# cryptocape.net
KiCad netlist of a schematic drawn in EAGLE
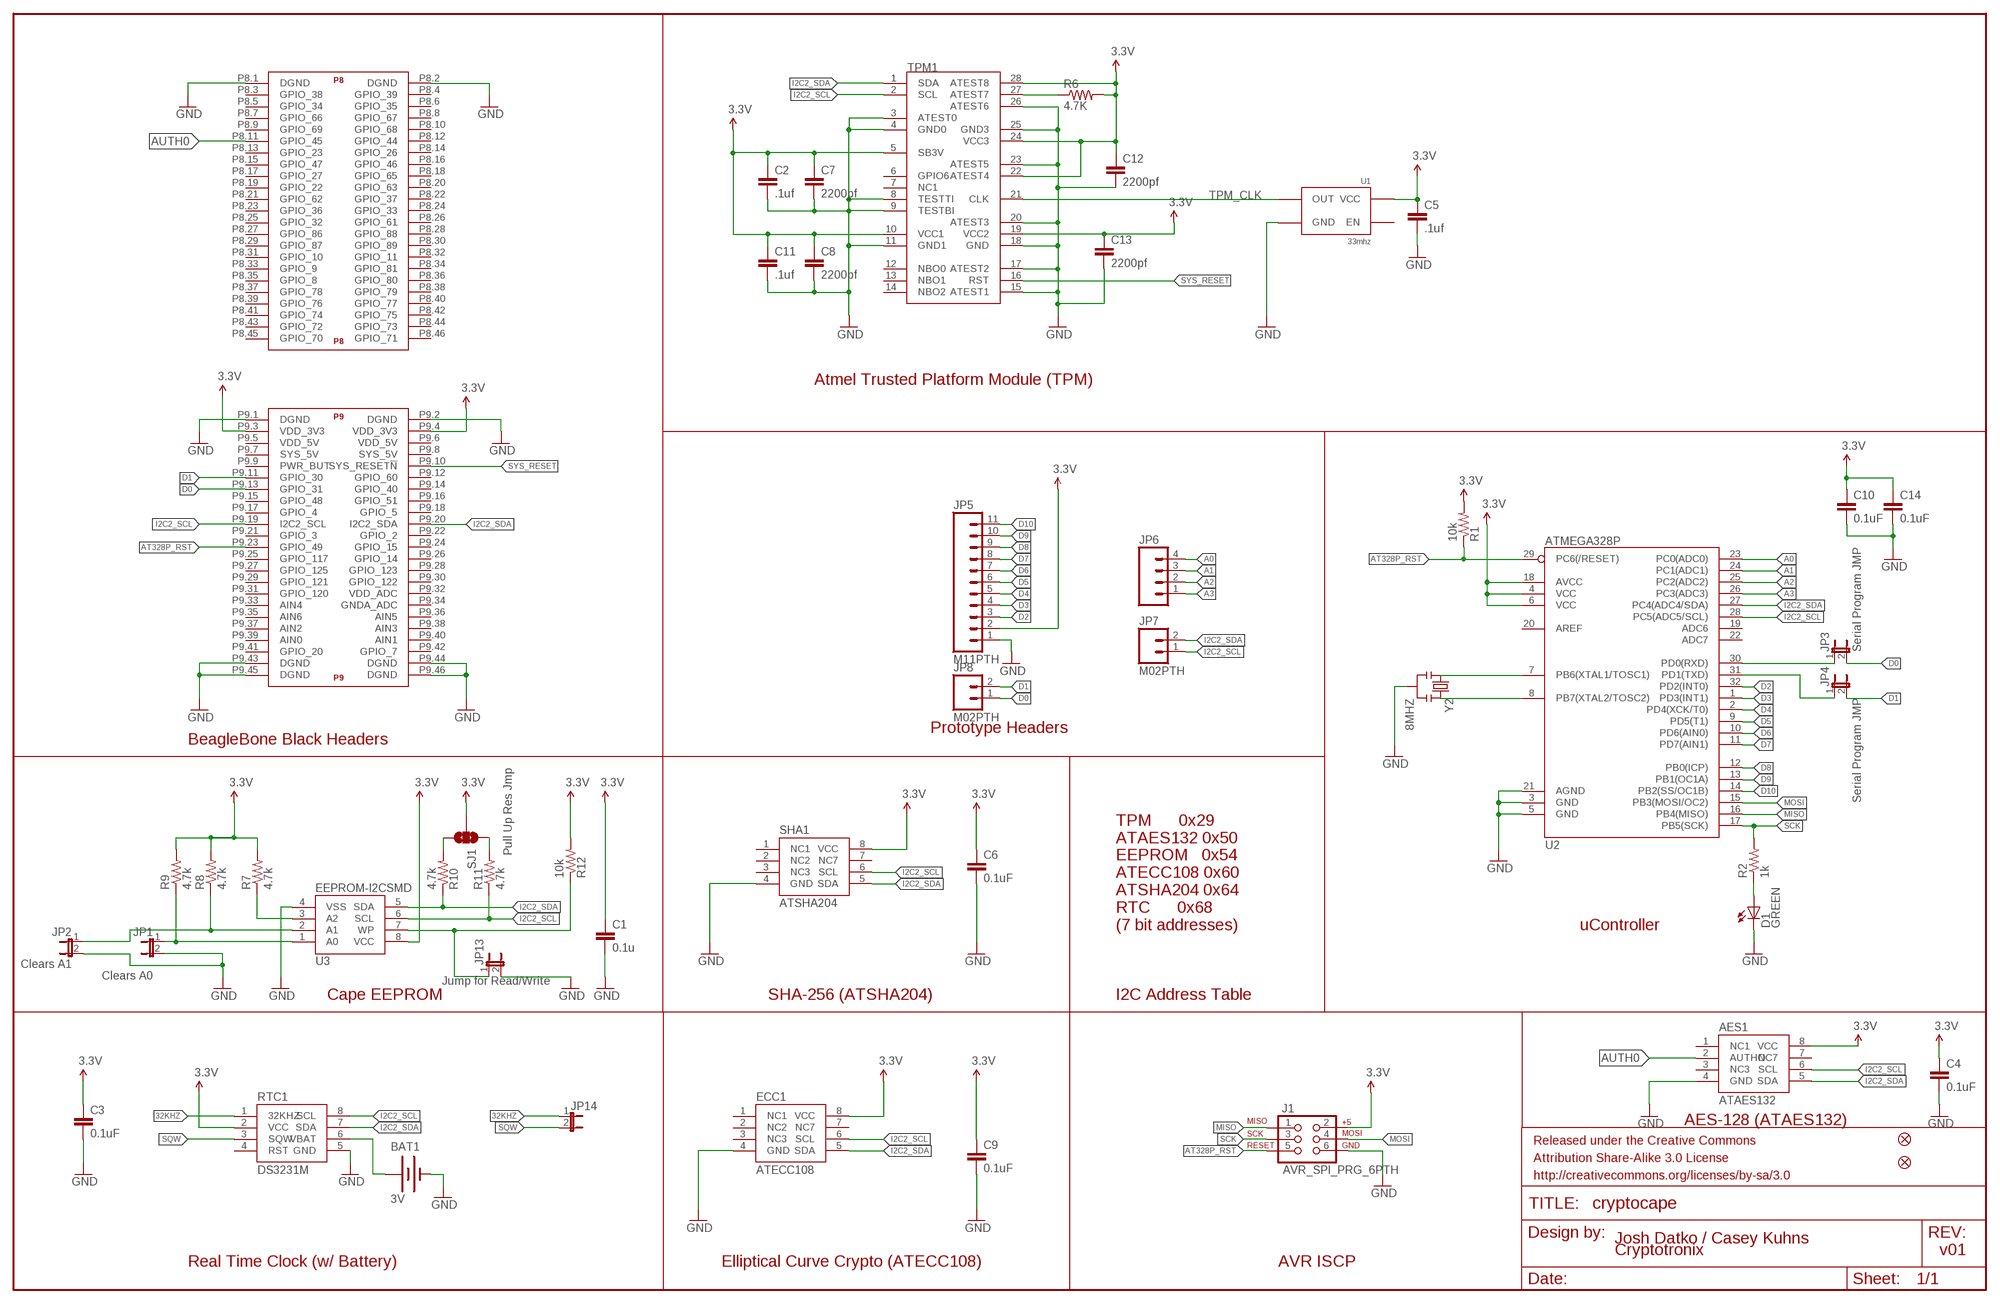
[diagram p0: schematic, sheet 1]

(export (version "E")
  (design (tool "Eeschema 10.0.6"))
  (components
    (comp (ref "AES1")
      (value "ATAES132")
      (footprint "eagle-import:SOIC8")
      (libsource (lib "eagle-import") (part "ATAES132"))
    )
    (comp (ref "BAT1")
      (value "3V")
      (footprint "eagle-import:BATTCON_12MM")
      (libsource (lib "eagle-import") (part "BATTERY12MM"))
    )
    (comp (ref "C1")
      (value "0.1u")
      (footprint "eagle-import:0603-CAP")
      (libsource (lib "eagle-import") (part "0.1UF-25V(+80/-20%)(0603)"))
    )
    (comp (ref "C2")
      (value ".1uf")
      (footprint "eagle-import:0603-CAP")
      (libsource (lib "eagle-import") (part "0.1UF-25V(+80/-20%)(0603)"))
    )
    (comp (ref "C3")
      (value "0.1uF")
      (footprint "eagle-import:0603-CAP")
      (libsource (lib "eagle-import") (part "0.1UF-25V(+80/-20%)(0603)"))
    )
    (comp (ref "C4")
      (value "0.1uF")
      (footprint "eagle-import:0603-CAP")
      (libsource (lib "eagle-import") (part "0.1UF-25V(+80/-20%)(0603)"))
    )
    (comp (ref "C5")
      (value ".1uf")
      (footprint "eagle-import:0603-CAP")
      (libsource (lib "eagle-import") (part "0.1UF-25V(+80/-20%)(0603)"))
    )
    (comp (ref "C6")
      (value "0.1uF")
      (footprint "eagle-import:0603-CAP")
      (libsource (lib "eagle-import") (part "0.1UF-25V(+80/-20%)(0603)"))
    )
    (comp (ref "C7")
      (value "2200pf")
      (footprint "eagle-import:0603-CAP")
      (libsource (lib "eagle-import") (part "2.2NF/2200PF-50V-10%(0603)"))
    )
    (comp (ref "C8")
      (value "2200pf")
      (footprint "eagle-import:0603-CAP")
      (libsource (lib "eagle-import") (part "2.2NF/2200PF-50V-10%(0603)"))
    )
    (comp (ref "C9")
      (value "0.1uF")
      (footprint "eagle-import:0603-CAP")
      (libsource (lib "eagle-import") (part "0.1UF-25V(+80/-20%)(0603)"))
    )
    (comp (ref "C10")
      (value "0.1uF")
      (footprint "eagle-import:0603-CAP")
      (libsource (lib "eagle-import") (part "0.1UF-25V(+80/-20%)(0603)"))
    )
    (comp (ref "C11")
      (value ".1uf")
      (footprint "eagle-import:0603-CAP")
      (libsource (lib "eagle-import") (part "0.1UF-25V(+80/-20%)(0603)"))
    )
    (comp (ref "C12")
      (value "2200pf")
      (footprint "eagle-import:0603-CAP")
      (libsource (lib "eagle-import") (part "2.2NF/2200PF-50V-10%(0603)"))
    )
    (comp (ref "C13")
      (value "2200pf")
      (footprint "eagle-import:0603-CAP")
      (libsource (lib "eagle-import") (part "2.2NF/2200PF-50V-10%(0603)"))
    )
    (comp (ref "C14")
      (value "0.1uF")
      (footprint "eagle-import:0603-CAP")
      (libsource (lib "eagle-import") (part "0.1UF-25V(+80/-20%)(0603)"))
    )
    (comp (ref "D1")
      (value "GREEN")
      (footprint "eagle-import:LED-0603")
      (libsource (lib "eagle-import") (part "LED-GREEN0603"))
    )
    (comp (ref "ECC1")
      (value "ATECC108")
      (footprint "eagle-import:SOIC8")
      (libsource (lib "eagle-import") (part "ATECC108"))
    )
    (comp (ref "FID1")
      (value "FIDUCIAL1X2")
      (footprint "eagle-import:FIDUCIAL-1X2")
      (libsource (lib "eagle-import") (part "FIDUCIAL1X2"))
    )
    (comp (ref "FID2")
      (value "FIDUCIAL1X2")
      (footprint "eagle-import:FIDUCIAL-1X2")
      (libsource (lib "eagle-import") (part "FIDUCIAL1X2"))
    )
    (comp (ref "FRAME1")
      (value "FRAME-LEDGER")
      (footprint "eagle-import:CREATIVE_COMMONS")
      (libsource (lib "eagle-import") (part "FRAME-LEDGER"))
    )
    (comp (ref "J1")
      (value "AVR_SPI_PRG_6PTH")
      (footprint "eagle-import:2X3")
      (libsource (lib "eagle-import") (part "AVR_SPI_PRG_6PTH"))
    )
    (comp (ref "JP1")
      (value "Clears A0")
      (footprint "eagle-import:SJ_2S-NO")
      (libsource (lib "eagle-import") (part "JUMPER-2SMD-NO"))
    )
    (comp (ref "JP2")
      (value "Clears A1")
      (footprint "eagle-import:SJ_2S-NO")
      (libsource (lib "eagle-import") (part "JUMPER-2SMD-NO"))
    )
    (comp (ref "JP3")
      (value "Serial Program JMP")
      (footprint "eagle-import:1X02")
      (libsource (lib "eagle-import") (part "JUMPER-2PTH"))
    )
    (comp (ref "JP4")
      (value "Serial Program JMP")
      (footprint "eagle-import:1X02")
      (libsource (lib "eagle-import") (part "JUMPER-2PTH"))
    )
    (comp (ref "JP5")
      (value "M11PTH")
      (footprint "eagle-import:1X11")
      (libsource (lib "eagle-import") (part "M11PTH"))
    )
    (comp (ref "JP6")
      (value "M04PTH")
      (footprint "eagle-import:1X04")
      (libsource (lib "eagle-import") (part "M04PTH"))
    )
    (comp (ref "JP7")
      (value "M02PTH")
      (footprint "eagle-import:1X02")
      (libsource (lib "eagle-import") (part "M02PTH"))
    )
    (comp (ref "JP8")
      (value "M02PTH")
      (footprint "eagle-import:1X02")
      (libsource (lib "eagle-import") (part "M02PTH"))
    )
    (comp (ref "JP13")
      (value "Jump for Read/Write")
      (footprint "eagle-import:1X02")
      (libsource (lib "eagle-import") (part "JUMPER-2PTH"))
    )
    (comp (ref "JP14")
      (value "JUMPER-2PTH")
      (footprint "eagle-import:1X02")
      (libsource (lib "eagle-import") (part "JUMPER-2PTH"))
    )
    (comp (ref "R1")
      (value "10k")
      (footprint "eagle-import:0603-RES")
      (libsource (lib "eagle-import") (part "10KOHM1/10W1%(0603)0603"))
    )
    (comp (ref "R2")
      (value "1k")
      (footprint "eagle-import:0603-RES")
      (libsource (lib "eagle-import") (part "1K-1%"))
    )
    (comp (ref "R6")
      (value "4.7K")
      (footprint "eagle-import:0603")
      (libsource (lib "eagle-import") (part "4.7KOHM1/10W1%(0603)"))
    )
    (comp (ref "R7")
      (value "4.7k")
      (footprint "eagle-import:0603")
      (libsource (lib "eagle-import") (part "4.7KOHM1/10W1%(0603)"))
    )
    (comp (ref "R8")
      (value "4.7k")
      (footprint "eagle-import:0603")
      (libsource (lib "eagle-import") (part "4.7KOHM1/10W1%(0603)"))
    )
    (comp (ref "R9")
      (value "4.7k")
      (footprint "eagle-import:0603")
      (libsource (lib "eagle-import") (part "4.7KOHM1/10W1%(0603)"))
    )
    (comp (ref "R10")
      (value "4.7k")
      (footprint "eagle-import:0603")
      (fields (field (name "PROD_ID") "RES-07857"))
      (libsource (lib "eagle-import") (part "4.7KOHM1/10W1%(0603)"))
    )
    (comp (ref "R11")
      (value "4.7k")
      (footprint "eagle-import:0603")
      (fields (field (name "PROD_ID") "RES-07857"))
      (libsource (lib "eagle-import") (part "4.7KOHM1/10W1%(0603)"))
    )
    (comp (ref "R12")
      (value "10k")
      (footprint "eagle-import:0603-RES")
      (libsource (lib "eagle-import") (part "10KOHM1/10W1%(0603)0603"))
    )
    (comp (ref "RTC1")
      (value "DS3231M")
      (footprint "eagle-import:SOIC8")
      (libsource (lib "eagle-import") (part "DS3231M"))
    )
    (comp (ref "SHA1")
      (value "ATSHA204")
      (footprint "eagle-import:SOIC8")
      (libsource (lib "eagle-import") (part "ATSHA204"))
    )
    (comp (ref "SJ1")
      (value "Pull Up Res Jmp")
      (footprint "eagle-import:SJ_3_PASTE1&2&3")
      (libsource (lib "eagle-import") (part "SOLDERJUMPER_2WAYPASTE1&2&3"))
    )
    (comp (ref "TPM1")
      (value "AT97SC3204T")
      (footprint "eagle-import:TSSOP28")
      (libsource (lib "eagle-import") (part "AT97SC3204T"))
    )
    (comp (ref "U$2")
      (value "BEAGLE_BONE_BLACK_CAPE")
      (footprint "eagle-import:BEAGLE_BONE_BLACK_CAPE")
      (libsource (lib "eagle-import") (part "BEAGLE_BONE_BLACK_CAPE"))
    )
    (comp (ref "U1")
      (value "33mhz")
      (footprint "eagle-import:CRYSTAL-OSC-SMD-5X3.2")
      (libsource (lib "eagle-import") (part "OSCILLATOR"))
    )
    (comp (ref "U2")
      (value "ATMEGA328P")
      (footprint "eagle-import:TQFP32-08")
      (libsource (lib "eagle-import") (part "ATMEGA328_SMT"))
    )
    (comp (ref "U3")
      (value "EEPROM-I2CSMD")
      (footprint "eagle-import:SO08")
      (libsource (lib "eagle-import") (part "EEPROM-I2CSMD"))
    )
    (comp (ref "Y2")
      (value "8MHZ")
      (footprint "eagle-import:RESONATOR-SMD")
      (libsource (lib "eagle-import") (part "RESONATOR8MHZ"))
    )
  )
  (nets
    (net (code "1") (name "/TPM_CLK") (class "Default")
      (node (ref "TPM1") (pin "21") (pinfunction "CLK_21") (pintype "bidirectional"))
      (node (ref "U1") (pin "3") (pinfunction "OUT_3") (pintype "bidirectional"))
    )
    (net (code "2") (name "3.3V") (class "Default")
      (node (ref "AES1") (pin "8") (pinfunction "VCC_8") (pintype "power_in"))
      (node (ref "C1") (pin "1") (pinfunction "1_1") (pintype "passive"))
      (node (ref "C10") (pin "1") (pinfunction "1_1") (pintype "passive"))
      (node (ref "C11") (pin "1") (pinfunction "1_1") (pintype "passive"))
      (node (ref "C12") (pin "1") (pinfunction "1_1") (pintype "passive"))
      (node (ref "C13") (pin "1") (pinfunction "1_1") (pintype "passive"))
      (node (ref "C14") (pin "1") (pinfunction "1_1") (pintype "passive"))
      (node (ref "C2") (pin "1") (pinfunction "1_1") (pintype "passive"))
      (node (ref "C3") (pin "1") (pinfunction "1_1") (pintype "passive"))
      (node (ref "C4") (pin "1") (pinfunction "1_1") (pintype "passive"))
      (node (ref "C5") (pin "1") (pinfunction "1_1") (pintype "passive"))
      (node (ref "C6") (pin "1") (pinfunction "1_1") (pintype "passive"))
      (node (ref "C7") (pin "1") (pinfunction "1_1") (pintype "passive"))
      (node (ref "C8") (pin "1") (pinfunction "1_1") (pintype "passive"))
      (node (ref "C9") (pin "1") (pinfunction "1_1") (pintype "passive"))
      (node (ref "ECC1") (pin "8") (pinfunction "VCC_8") (pintype "power_in"))
      (node (ref "J1") (pin "2") (pinfunction "2_2") (pintype "passive"))
      (node (ref "JP5") (pin "2") (pinfunction "2_2") (pintype "passive"))
      (node (ref "R1") (pin "2") (pinfunction "2_2") (pintype "passive"))
      (node (ref "R12") (pin "2") (pinfunction "2_2") (pintype "passive"))
      (node (ref "R6") (pin "2") (pinfunction "2_2") (pintype "passive"))
      (node (ref "R7") (pin "2") (pinfunction "2_2") (pintype "passive"))
      (node (ref "R8") (pin "2") (pinfunction "2_2") (pintype "passive"))
      (node (ref "R9") (pin "2") (pinfunction "2_2") (pintype "passive"))
      (node (ref "RTC1") (pin "2") (pinfunction "VCC_2") (pintype "power_in"))
      (node (ref "SHA1") (pin "8") (pinfunction "VCC_8") (pintype "power_in"))
      (node (ref "SJ1") (pin "2") (pinfunction "2_2") (pintype "passive"))
      (node (ref "TPM1") (pin "10") (pinfunction "VCC1_10") (pintype "power_in"))
      (node (ref "TPM1") (pin "19") (pinfunction "VCC2_19") (pintype "power_in"))
      (node (ref "TPM1") (pin "22") (pinfunction "ATEST4_22") (pintype "power_in"))
      (node (ref "TPM1") (pin "24") (pinfunction "VCC3_24") (pintype "power_in"))
      (node (ref "TPM1") (pin "28") (pinfunction "ATEST8_28") (pintype "power_in"))
      (node (ref "TPM1") (pin "5") (pinfunction "SB3V_5") (pintype "power_in"))
      (node (ref "U$2") (pin "P9.3") (pinfunction "VDD_3V3_P9.3") (pintype "bidirectional"))
      (node (ref "U$2") (pin "P9.4") (pinfunction "VDD_3V3_P9.4") (pintype "bidirectional"))
      (node (ref "U1") (pin "4") (pinfunction "VCC_4") (pintype "bidirectional"))
      (node (ref "U2") (pin "18") (pinfunction "AVCC_18") (pintype "bidirectional"))
      (node (ref "U2") (pin "4") (pinfunction "VCC_4") (pintype "bidirectional"))
      (node (ref "U2") (pin "6") (pinfunction "VCC_6") (pintype "bidirectional"))
      (node (ref "U3") (pin "8") (pinfunction "VCC_8") (pintype "power_in"))
    )
    (net (code "3") (name "32KHZ") (class "Default")
      (node (ref "JP14") (pin "1") (pinfunction "1_1") (pintype "passive"))
      (node (ref "RTC1") (pin "1") (pinfunction "32KHZ_1") (pintype "output"))
    )
    (net (code "4") (name "A0") (class "Default")
      (node (ref "JP6") (pin "4") (pinfunction "4_4") (pintype "passive"))
      (node (ref "U2") (pin "23") (pinfunction "PC0(ADC0)_23") (pintype "bidirectional"))
    )
    (net (code "5") (name "A1") (class "Default")
      (node (ref "JP6") (pin "3") (pinfunction "3_3") (pintype "passive"))
      (node (ref "U2") (pin "24") (pinfunction "PC1(ADC1)_24") (pintype "bidirectional"))
    )
    (net (code "6") (name "A2") (class "Default")
      (node (ref "JP6") (pin "2") (pinfunction "2_2") (pintype "passive"))
      (node (ref "U2") (pin "25") (pinfunction "PC2(ADC2)_25") (pintype "bidirectional"))
    )
    (net (code "7") (name "A3") (class "Default")
      (node (ref "JP6") (pin "1") (pinfunction "1_1") (pintype "passive"))
      (node (ref "U2") (pin "26") (pinfunction "PC3(ADC3)_26") (pintype "bidirectional"))
    )
    (net (code "8") (name "AT328P_RST") (class "Default")
      (node (ref "J1") (pin "5") (pinfunction "5_5") (pintype "passive"))
      (node (ref "R1") (pin "1") (pinfunction "1_1") (pintype "passive"))
      (node (ref "U$2") (pin "P9.23") (pinfunction "GPIO_49_P9.23") (pintype "bidirectional"))
      (node (ref "U2") (pin "29") (pinfunction "PC6(/RESET)_29") (pintype "bidirectional"))
    )
    (net (code "9") (name "AUTH0") (class "Default")
      (node (ref "AES1") (pin "2") (pinfunction "AUTHO_2") (pintype "bidirectional"))
      (node (ref "U$2") (pin "P8.11") (pinfunction "GPIO_45_P8.11") (pintype "bidirectional"))
    )
    (net (code "10") (name "D0") (class "Default")
      (node (ref "JP3") (pin "2") (pinfunction "2_2") (pintype "passive"))
      (node (ref "JP8") (pin "1") (pinfunction "1_1") (pintype "passive"))
      (node (ref "U$2") (pin "P9.13") (pinfunction "GPIO_31_P9.13") (pintype "bidirectional"))
    )
    (net (code "11") (name "D1") (class "Default")
      (node (ref "JP4") (pin "2") (pinfunction "2_2") (pintype "passive"))
      (node (ref "JP8") (pin "2") (pinfunction "2_2") (pintype "passive"))
      (node (ref "U$2") (pin "P9.11") (pinfunction "GPIO_30_P9.11") (pintype "bidirectional"))
    )
    (net (code "12") (name "D2") (class "Default")
      (node (ref "JP5") (pin "3") (pinfunction "3_3") (pintype "passive"))
      (node (ref "U2") (pin "32") (pinfunction "PD2(INT0)_32") (pintype "bidirectional"))
    )
    (net (code "13") (name "D3") (class "Default")
      (node (ref "JP5") (pin "4") (pinfunction "4_4") (pintype "passive"))
      (node (ref "U2") (pin "1") (pinfunction "PD3(INT1)_1") (pintype "bidirectional"))
    )
    (net (code "14") (name "D4") (class "Default")
      (node (ref "JP5") (pin "5") (pinfunction "5_5") (pintype "passive"))
      (node (ref "U2") (pin "2") (pinfunction "PD4(XCK/T0)_2") (pintype "bidirectional"))
    )
    (net (code "15") (name "D5") (class "Default")
      (node (ref "JP5") (pin "6") (pinfunction "6_6") (pintype "passive"))
      (node (ref "U2") (pin "9") (pinfunction "PD5(T1)_9") (pintype "bidirectional"))
    )
    (net (code "16") (name "D6") (class "Default")
      (node (ref "JP5") (pin "7") (pinfunction "7_7") (pintype "passive"))
      (node (ref "U2") (pin "10") (pinfunction "PD6(AIN0)_10") (pintype "bidirectional"))
    )
    (net (code "17") (name "D7") (class "Default")
      (node (ref "JP5") (pin "8") (pinfunction "8_8") (pintype "passive"))
      (node (ref "U2") (pin "11") (pinfunction "PD7(AIN1)_11") (pintype "bidirectional"))
    )
    (net (code "18") (name "D8") (class "Default")
      (node (ref "JP5") (pin "9") (pinfunction "9_9") (pintype "passive"))
      (node (ref "U2") (pin "12") (pinfunction "PB0(ICP)_12") (pintype "bidirectional"))
    )
    (net (code "19") (name "D9") (class "Default")
      (node (ref "JP5") (pin "10") (pinfunction "10_10") (pintype "passive"))
      (node (ref "U2") (pin "13") (pinfunction "PB1(OC1A)_13") (pintype "bidirectional"))
    )
    (net (code "20") (name "D10") (class "Default")
      (node (ref "JP5") (pin "11") (pinfunction "11_11") (pintype "passive"))
      (node (ref "U2") (pin "14") (pinfunction "PB2(SS/OC1B)_14") (pintype "bidirectional"))
    )
    (net (code "21") (name "GND") (class "Default")
      (node (ref "AES1") (pin "4") (pinfunction "GND_4") (pintype "power_in"))
      (node (ref "BAT1") (pin "GND") (pinfunction "-_GND") (pintype "power_in"))
      (node (ref "C1") (pin "2") (pinfunction "2_2") (pintype "passive"))
      (node (ref "C10") (pin "2") (pinfunction "2_2") (pintype "passive"))
      (node (ref "C11") (pin "2") (pinfunction "2_2") (pintype "passive"))
      (node (ref "C12") (pin "2") (pinfunction "2_2") (pintype "passive"))
      (node (ref "C13") (pin "2") (pinfunction "2_2") (pintype "passive"))
      (node (ref "C14") (pin "2") (pinfunction "2_2") (pintype "passive"))
      (node (ref "C2") (pin "2") (pinfunction "2_2") (pintype "passive"))
      (node (ref "C3") (pin "2") (pinfunction "2_2") (pintype "passive"))
      (node (ref "C4") (pin "2") (pinfunction "2_2") (pintype "passive"))
      (node (ref "C5") (pin "2") (pinfunction "2_2") (pintype "passive"))
      (node (ref "C6") (pin "2") (pinfunction "2_2") (pintype "passive"))
      (node (ref "C7") (pin "2") (pinfunction "2_2") (pintype "passive"))
      (node (ref "C8") (pin "2") (pinfunction "2_2") (pintype "passive"))
      (node (ref "C9") (pin "2") (pinfunction "2_2") (pintype "passive"))
      (node (ref "D1") (pin "C") (pinfunction "C_C") (pintype "passive"))
      (node (ref "ECC1") (pin "4") (pinfunction "GND_4") (pintype "power_in"))
      (node (ref "J1") (pin "6") (pinfunction "6_6") (pintype "passive"))
      (node (ref "JP1") (pin "2") (pinfunction "2_2") (pintype "passive"))
      (node (ref "JP13") (pin "2") (pinfunction "2_2") (pintype "passive"))
      (node (ref "JP2") (pin "2") (pinfunction "2_2") (pintype "passive"))
      (node (ref "JP5") (pin "1") (pinfunction "1_1") (pintype "passive"))
      (node (ref "RTC1") (pin "5") (pinfunction "GND_5") (pintype "power_in"))
      (node (ref "SHA1") (pin "4") (pinfunction "GND_4") (pintype "power_in"))
      (node (ref "TPM1") (pin "11") (pinfunction "GND1_11") (pintype "power_in"))
      (node (ref "TPM1") (pin "15") (pinfunction "ATEST1_15") (pintype "power_in"))
      (node (ref "TPM1") (pin "17") (pinfunction "ATEST2_17") (pintype "power_in"))
      (node (ref "TPM1") (pin "18") (pinfunction "GND_18") (pintype "power_in"))
      (node (ref "TPM1") (pin "20") (pinfunction "ATEST3_20") (pintype "power_in"))
      (node (ref "TPM1") (pin "23") (pinfunction "ATEST5_23") (pintype "power_in"))
      (node (ref "TPM1") (pin "25") (pinfunction "GND3_25") (pintype "power_in"))
      (node (ref "TPM1") (pin "26") (pinfunction "ATEST6_26") (pintype "power_in"))
      (node (ref "TPM1") (pin "3") (pinfunction "ATEST0_3") (pintype "power_in"))
      (node (ref "TPM1") (pin "4") (pinfunction "GND0_4") (pintype "power_in"))
      (node (ref "TPM1") (pin "8") (pinfunction "TESTTI_8") (pintype "power_in"))
      (node (ref "TPM1") (pin "9") (pinfunction "TESTBI_9") (pintype "power_in"))
      (node (ref "U$2") (pin "P8.1") (pinfunction "DGND_P8.1") (pintype "bidirectional"))
      (node (ref "U$2") (pin "P8.2") (pinfunction "DGND_P8.2") (pintype "bidirectional"))
      (node (ref "U$2") (pin "P9.1") (pinfunction "DGND_P9.1") (pintype "bidirectional"))
      (node (ref "U$2") (pin "P9.2") (pinfunction "DGND_P9.2") (pintype "bidirectional"))
      (node (ref "U$2") (pin "P9.43") (pinfunction "DGND_P9.43") (pintype "bidirectional"))
      (node (ref "U$2") (pin "P9.44") (pinfunction "DGND_P9.44") (pintype "bidirectional"))
      (node (ref "U$2") (pin "P9.45") (pinfunction "DGND_P9.45") (pintype "bidirectional"))
      (node (ref "U$2") (pin "P9.46") (pinfunction "DGND_P9.46") (pintype "bidirectional"))
      (node (ref "U1") (pin "2") (pinfunction "GND_2") (pintype "bidirectional"))
      (node (ref "U2") (pin "21") (pinfunction "AGND_21") (pintype "bidirectional"))
      (node (ref "U2") (pin "3") (pinfunction "GND_3") (pintype "bidirectional"))
      (node (ref "U2") (pin "5") (pinfunction "GND_5") (pintype "bidirectional"))
      (node (ref "U3") (pin "4") (pinfunction "VSS_4") (pintype "power_in"))
      (node (ref "Y2") (pin "2") (pinfunction "2_2") (pintype "passive"))
    )
    (net (code "22") (name "I2C2_SCL") (class "Default")
      (node (ref "AES1") (pin "6") (pinfunction "SCL_6") (pintype "bidirectional"))
      (node (ref "ECC1") (pin "6") (pinfunction "SCL_6") (pintype "bidirectional"))
      (node (ref "JP7") (pin "1") (pinfunction "1_1") (pintype "passive"))
      (node (ref "R11") (pin "1") (pinfunction "1_1") (pintype "passive"))
      (node (ref "RTC1") (pin "8") (pinfunction "SCL_8") (pintype "bidirectional"))
      (node (ref "SHA1") (pin "6") (pinfunction "SCL_6") (pintype "bidirectional"))
      (node (ref "TPM1") (pin "2") (pinfunction "SCL_2") (pintype "bidirectional"))
      (node (ref "U$2") (pin "P9.19") (pinfunction "I2C2_SCL_P9.19") (pintype "bidirectional"))
      (node (ref "U2") (pin "28") (pinfunction "PC5(ADC5/SCL)_28") (pintype "bidirectional"))
      (node (ref "U3") (pin "6") (pinfunction "SCL_6") (pintype "bidirectional"))
    )
    (net (code "23") (name "I2C2_SDA") (class "Default")
      (node (ref "AES1") (pin "5") (pinfunction "SDA_5") (pintype "bidirectional"))
      (node (ref "ECC1") (pin "5") (pinfunction "SDA_5") (pintype "bidirectional"))
      (node (ref "JP7") (pin "2") (pinfunction "2_2") (pintype "passive"))
      (node (ref "R10") (pin "1") (pinfunction "1_1") (pintype "passive"))
      (node (ref "RTC1") (pin "7") (pinfunction "SDA_7") (pintype "bidirectional"))
      (node (ref "SHA1") (pin "5") (pinfunction "SDA_5") (pintype "bidirectional"))
      (node (ref "TPM1") (pin "1") (pinfunction "SDA_1") (pintype "bidirectional"))
      (node (ref "U$2") (pin "P9.20") (pinfunction "I2C2_SDA_P9.20") (pintype "bidirectional"))
      (node (ref "U2") (pin "27") (pinfunction "PC4(ADC4/SDA)_27") (pintype "bidirectional"))
      (node (ref "U3") (pin "5") (pinfunction "SDA_5") (pintype "bidirectional"))
    )
    (net (code "24") (name "MISO") (class "Default")
      (node (ref "J1") (pin "1") (pinfunction "1_1") (pintype "passive"))
      (node (ref "U2") (pin "16") (pinfunction "PB4(MISO)_16") (pintype "bidirectional"))
    )
    (net (code "25") (name "MOSI") (class "Default")
      (node (ref "J1") (pin "4") (pinfunction "4_4") (pintype "passive"))
      (node (ref "U2") (pin "15") (pinfunction "PB3(MOSI/OC2)_15") (pintype "bidirectional"))
    )
    (net (code "26") (name "Net-(BAT1-+)") (class "Default")
      (node (ref "BAT1") (pin "PWR@1") (pinfunction "+_PWR@1") (pintype "power_in"))
      (node (ref "RTC1") (pin "6") (pinfunction "VBAT_6") (pintype "power_in"))
    )
    (net (code "27") (name "Net-(D1-PadA)") (class "Default")
      (node (ref "D1") (pin "A") (pinfunction "A_A") (pintype "passive"))
      (node (ref "R2") (pin "1") (pinfunction "1_1") (pintype "passive"))
    )
    (net (code "28") (name "Net-(R10-Pad2)") (class "Default")
      (node (ref "R10") (pin "2") (pinfunction "2_2") (pintype "passive"))
      (node (ref "SJ1") (pin "3") (pinfunction "3_3") (pintype "passive"))
    )
    (net (code "29") (name "Net-(R11-Pad2)") (class "Default")
      (node (ref "R11") (pin "2") (pinfunction "2_2") (pintype "passive"))
      (node (ref "SJ1") (pin "1") (pinfunction "1_1") (pintype "passive"))
    )
    (net (code "30") (name "Net-(TPM1-ATEST7)") (class "Default")
      (node (ref "R6") (pin "1") (pinfunction "1_1") (pintype "passive"))
      (node (ref "TPM1") (pin "27") (pinfunction "ATEST7_27") (pintype "power_in"))
    )
    (net (code "31") (name "Net-(U2-PB6(XTAL1{slash}TOSC1))") (class "Default")
      (node (ref "U2") (pin "7") (pinfunction "PB6(XTAL1/TOSC1)_7") (pintype "bidirectional"))
      (node (ref "Y2") (pin "1") (pinfunction "1_1") (pintype "passive"))
    )
    (net (code "32") (name "Net-(U2-PB7(XTAL2{slash}TOSC2))") (class "Default")
      (node (ref "U2") (pin "8") (pinfunction "PB7(XTAL2/TOSC2)_8") (pintype "bidirectional"))
      (node (ref "Y2") (pin "3") (pinfunction "3_3") (pintype "passive"))
    )
    (net (code "33") (name "Net-(U2-PD0(RXD))") (class "Default")
      (node (ref "JP3") (pin "1") (pinfunction "1_1") (pintype "passive"))
      (node (ref "U2") (pin "30") (pinfunction "PD0(RXD)_30") (pintype "bidirectional"))
    )
    (net (code "34") (name "Net-(U2-PD1(TXD))") (class "Default")
      (node (ref "JP4") (pin "1") (pinfunction "1_1") (pintype "passive"))
      (node (ref "U2") (pin "31") (pinfunction "PD1(TXD)_31") (pintype "bidirectional"))
    )
    (net (code "35") (name "Net-(U3-A0)") (class "Default")
      (node (ref "JP1") (pin "1") (pinfunction "1_1") (pintype "passive"))
      (node (ref "R9") (pin "1") (pinfunction "1_1") (pintype "passive"))
      (node (ref "U3") (pin "1") (pinfunction "A0_1") (pintype "bidirectional"))
    )
    (net (code "36") (name "Net-(U3-A1)") (class "Default")
      (node (ref "JP2") (pin "1") (pinfunction "1_1") (pintype "passive"))
      (node (ref "R8") (pin "1") (pinfunction "1_1") (pintype "passive"))
      (node (ref "U3") (pin "2") (pinfunction "A1_2") (pintype "bidirectional"))
    )
    (net (code "37") (name "Net-(U3-A2)") (class "Default")
      (node (ref "R7") (pin "1") (pinfunction "1_1") (pintype "passive"))
      (node (ref "U3") (pin "3") (pinfunction "A2_3") (pintype "bidirectional"))
    )
    (net (code "38") (name "Net-(U3-WP)") (class "Default")
      (node (ref "JP13") (pin "1") (pinfunction "1_1") (pintype "passive"))
      (node (ref "R12") (pin "1") (pinfunction "1_1") (pintype "passive"))
      (node (ref "U3") (pin "7") (pinfunction "WP_7") (pintype "bidirectional"))
    )
    (net (code "39") (name "SCK") (class "Default")
      (node (ref "J1") (pin "3") (pinfunction "3_3") (pintype "passive"))
      (node (ref "R2") (pin "2") (pinfunction "2_2") (pintype "passive"))
      (node (ref "U2") (pin "17") (pinfunction "PB5(SCK)_17") (pintype "bidirectional"))
    )
    (net (code "40") (name "SQW") (class "Default")
      (node (ref "JP14") (pin "2") (pinfunction "2_2") (pintype "passive"))
      (node (ref "RTC1") (pin "3") (pinfunction "SQW_3") (pintype "output"))
    )
    (net (code "41") (name "SYS_RESET") (class "Default")
      (node (ref "TPM1") (pin "16") (pinfunction "RST_16") (pintype "bidirectional"))
      (node (ref "U$2") (pin "P9.10") (pinfunction "SYS_RESET~{N}_P9.10") (pintype "bidirectional"))
    )
    (net (code "42") (name "unconnected-(AES1-NC1-Pad1)") (class "Default")
      (node (ref "AES1") (pin "1") (pinfunction "NC1_1") (pintype "no_connect"))
    )
    (net (code "43") (name "unconnected-(AES1-NC3-Pad3)") (class "Default")
      (node (ref "AES1") (pin "3") (pinfunction "NC3_3") (pintype "no_connect"))
    )
    (net (code "44") (name "unconnected-(AES1-NC7-Pad7)") (class "Default")
      (node (ref "AES1") (pin "7") (pinfunction "NC7_7") (pintype "no_connect"))
    )
    (net (code "45") (name "unconnected-(ECC1-NC1-Pad1)") (class "Default")
      (node (ref "ECC1") (pin "1") (pinfunction "NC1_1") (pintype "bidirectional"))
    )
    (net (code "46") (name "unconnected-(ECC1-NC2-Pad2)") (class "Default")
      (node (ref "ECC1") (pin "2") (pinfunction "NC2_2") (pintype "no_connect"))
    )
    (net (code "47") (name "unconnected-(ECC1-NC3-Pad3)") (class "Default")
      (node (ref "ECC1") (pin "3") (pinfunction "NC3_3") (pintype "no_connect"))
    )
    (net (code "48") (name "unconnected-(ECC1-NC7-Pad7)") (class "Default")
      (node (ref "ECC1") (pin "7") (pinfunction "NC7_7") (pintype "no_connect"))
    )
    (net (code "49") (name "unconnected-(RTC1-RST-Pad4)") (class "Default")
      (node (ref "RTC1") (pin "4") (pinfunction "RST_4") (pintype "bidirectional"))
    )
    (net (code "50") (name "unconnected-(SHA1-NC1-Pad1)") (class "Default")
      (node (ref "SHA1") (pin "1") (pinfunction "NC1_1") (pintype "no_connect"))
    )
    (net (code "51") (name "unconnected-(SHA1-NC2-Pad2)") (class "Default")
      (node (ref "SHA1") (pin "2") (pinfunction "NC2_2") (pintype "no_connect"))
    )
    (net (code "52") (name "unconnected-(SHA1-NC3-Pad3)") (class "Default")
      (node (ref "SHA1") (pin "3") (pinfunction "NC3_3") (pintype "no_connect"))
    )
    (net (code "53") (name "unconnected-(SHA1-NC7-Pad7)") (class "Default")
      (node (ref "SHA1") (pin "7") (pinfunction "NC7_7") (pintype "no_connect"))
    )
    (net (code "54") (name "unconnected-(TPM1-GPIO6-Pad6)") (class "Default")
      (node (ref "TPM1") (pin "6") (pinfunction "GPIO6_6") (pintype "bidirectional"))
    )
    (net (code "55") (name "unconnected-(TPM1-NBO0-Pad12)") (class "Default")
      (node (ref "TPM1") (pin "12") (pinfunction "NBO0_12") (pintype "no_connect"))
    )
    (net (code "56") (name "unconnected-(TPM1-NBO1-Pad13)") (class "Default")
      (node (ref "TPM1") (pin "13") (pinfunction "NBO1_13") (pintype "no_connect"))
    )
    (net (code "57") (name "unconnected-(TPM1-NBO2-Pad14)") (class "Default")
      (node (ref "TPM1") (pin "14") (pinfunction "NBO2_14") (pintype "no_connect"))
    )
    (net (code "58") (name "unconnected-(TPM1-NC1-Pad7)") (class "Default")
      (node (ref "TPM1") (pin "7") (pinfunction "NC1_7") (pintype "no_connect"))
    )
    (net (code "59") (name "unconnected-(U$2A-GPIO_8-PadP8.35)") (class "Default")
      (node (ref "U$2") (pin "P8.35") (pinfunction "GPIO_8_P8.35") (pintype "bidirectional"))
    )
    (net (code "60") (name "unconnected-(U$2A-GPIO_9-PadP8.33)") (class "Default")
      (node (ref "U$2") (pin "P8.33") (pinfunction "GPIO_9_P8.33") (pintype "bidirectional"))
    )
    (net (code "61") (name "unconnected-(U$2A-GPIO_10-PadP8.31)") (class "Default")
      (node (ref "U$2") (pin "P8.31") (pinfunction "GPIO_10_P8.31") (pintype "bidirectional"))
    )
    (net (code "62") (name "unconnected-(U$2A-GPIO_11-PadP8.32)") (class "Default")
      (node (ref "U$2") (pin "P8.32") (pinfunction "GPIO_11_P8.32") (pintype "bidirectional"))
    )
    (net (code "63") (name "unconnected-(U$2A-GPIO_22-PadP8.19)") (class "Default")
      (node (ref "U$2") (pin "P8.19") (pinfunction "GPIO_22_P8.19") (pintype "bidirectional"))
    )
    (net (code "64") (name "unconnected-(U$2A-GPIO_23-PadP8.13)") (class "Default")
      (node (ref "U$2") (pin "P8.13") (pinfunction "GPIO_23_P8.13") (pintype "bidirectional"))
    )
    (net (code "65") (name "unconnected-(U$2A-GPIO_26-PadP8.14)") (class "Default")
      (node (ref "U$2") (pin "P8.14") (pinfunction "GPIO_26_P8.14") (pintype "bidirectional"))
    )
    (net (code "66") (name "unconnected-(U$2A-GPIO_27-PadP8.17)") (class "Default")
      (node (ref "U$2") (pin "P8.17") (pinfunction "GPIO_27_P8.17") (pintype "bidirectional"))
    )
    (net (code "67") (name "unconnected-(U$2A-GPIO_32-PadP8.25)") (class "Default")
      (node (ref "U$2") (pin "P8.25") (pinfunction "GPIO_32_P8.25") (pintype "bidirectional"))
    )
    (net (code "68") (name "unconnected-(U$2A-GPIO_33-PadP8.24)") (class "Default")
      (node (ref "U$2") (pin "P8.24") (pinfunction "GPIO_33_P8.24") (pintype "bidirectional"))
    )
    (net (code "69") (name "unconnected-(U$2A-GPIO_34-PadP8.5)") (class "Default")
      (node (ref "U$2") (pin "P8.5") (pinfunction "GPIO_34_P8.5") (pintype "bidirectional"))
    )
    (net (code "70") (name "unconnected-(U$2A-GPIO_35-PadP8.6)") (class "Default")
      (node (ref "U$2") (pin "P8.6") (pinfunction "GPIO_35_P8.6") (pintype "bidirectional"))
    )
    (net (code "71") (name "unconnected-(U$2A-GPIO_36-PadP8.23)") (class "Default")
      (node (ref "U$2") (pin "P8.23") (pinfunction "GPIO_36_P8.23") (pintype "bidirectional"))
    )
    (net (code "72") (name "unconnected-(U$2A-GPIO_37-PadP8.22)") (class "Default")
      (node (ref "U$2") (pin "P8.22") (pinfunction "GPIO_37_P8.22") (pintype "bidirectional"))
    )
    (net (code "73") (name "unconnected-(U$2A-GPIO_38-PadP8.3)") (class "Default")
      (node (ref "U$2") (pin "P8.3") (pinfunction "GPIO_38_P8.3") (pintype "bidirectional"))
    )
    (net (code "74") (name "unconnected-(U$2A-GPIO_39-PadP8.4)") (class "Default")
      (node (ref "U$2") (pin "P8.4") (pinfunction "GPIO_39_P8.4") (pintype "bidirectional"))
    )
    (net (code "75") (name "unconnected-(U$2A-GPIO_44-PadP8.12)") (class "Default")
      (node (ref "U$2") (pin "P8.12") (pinfunction "GPIO_44_P8.12") (pintype "bidirectional"))
    )
    (net (code "76") (name "unconnected-(U$2A-GPIO_46-PadP8.16)") (class "Default")
      (node (ref "U$2") (pin "P8.16") (pinfunction "GPIO_46_P8.16") (pintype "bidirectional"))
    )
    (net (code "77") (name "unconnected-(U$2A-GPIO_47-PadP8.15)") (class "Default")
      (node (ref "U$2") (pin "P8.15") (pinfunction "GPIO_47_P8.15") (pintype "bidirectional"))
    )
    (net (code "78") (name "unconnected-(U$2A-GPIO_61-PadP8.26)") (class "Default")
      (node (ref "U$2") (pin "P8.26") (pinfunction "GPIO_61_P8.26") (pintype "bidirectional"))
    )
    (net (code "79") (name "unconnected-(U$2A-GPIO_62-PadP8.21)") (class "Default")
      (node (ref "U$2") (pin "P8.21") (pinfunction "GPIO_62_P8.21") (pintype "bidirectional"))
    )
    (net (code "80") (name "unconnected-(U$2A-GPIO_63-PadP8.20)") (class "Default")
      (node (ref "U$2") (pin "P8.20") (pinfunction "GPIO_63_P8.20") (pintype "bidirectional"))
    )
    (net (code "81") (name "unconnected-(U$2A-GPIO_65-PadP8.18)") (class "Default")
      (node (ref "U$2") (pin "P8.18") (pinfunction "GPIO_65_P8.18") (pintype "bidirectional"))
    )
    (net (code "82") (name "unconnected-(U$2A-GPIO_66-PadP8.7)") (class "Default")
      (node (ref "U$2") (pin "P8.7") (pinfunction "GPIO_66_P8.7") (pintype "bidirectional"))
    )
    (net (code "83") (name "unconnected-(U$2A-GPIO_67-PadP8.8)") (class "Default")
      (node (ref "U$2") (pin "P8.8") (pinfunction "GPIO_67_P8.8") (pintype "bidirectional"))
    )
    (net (code "84") (name "unconnected-(U$2A-GPIO_68-PadP8.10)") (class "Default")
      (node (ref "U$2") (pin "P8.10") (pinfunction "GPIO_68_P8.10") (pintype "bidirectional"))
    )
    (net (code "85") (name "unconnected-(U$2A-GPIO_69-PadP8.9)") (class "Default")
      (node (ref "U$2") (pin "P8.9") (pinfunction "GPIO_69_P8.9") (pintype "bidirectional"))
    )
    (net (code "86") (name "unconnected-(U$2A-GPIO_70-PadP8.45)") (class "Default")
      (node (ref "U$2") (pin "P8.45") (pinfunction "GPIO_70_P8.45") (pintype "bidirectional"))
    )
    (net (code "87") (name "unconnected-(U$2A-GPIO_71-PadP8.46)") (class "Default")
      (node (ref "U$2") (pin "P8.46") (pinfunction "GPIO_71_P8.46") (pintype "bidirectional"))
    )
    (net (code "88") (name "unconnected-(U$2A-GPIO_72-PadP8.43)") (class "Default")
      (node (ref "U$2") (pin "P8.43") (pinfunction "GPIO_72_P8.43") (pintype "bidirectional"))
    )
    (net (code "89") (name "unconnected-(U$2A-GPIO_73-PadP8.44)") (class "Default")
      (node (ref "U$2") (pin "P8.44") (pinfunction "GPIO_73_P8.44") (pintype "bidirectional"))
    )
    (net (code "90") (name "unconnected-(U$2A-GPIO_74-PadP8.41)") (class "Default")
      (node (ref "U$2") (pin "P8.41") (pinfunction "GPIO_74_P8.41") (pintype "bidirectional"))
    )
    (net (code "91") (name "unconnected-(U$2A-GPIO_75-PadP8.42)") (class "Default")
      (node (ref "U$2") (pin "P8.42") (pinfunction "GPIO_75_P8.42") (pintype "bidirectional"))
    )
    (net (code "92") (name "unconnected-(U$2A-GPIO_76-PadP8.39)") (class "Default")
      (node (ref "U$2") (pin "P8.39") (pinfunction "GPIO_76_P8.39") (pintype "bidirectional"))
    )
    (net (code "93") (name "unconnected-(U$2A-GPIO_77-PadP8.40)") (class "Default")
      (node (ref "U$2") (pin "P8.40") (pinfunction "GPIO_77_P8.40") (pintype "bidirectional"))
    )
    (net (code "94") (name "unconnected-(U$2A-GPIO_78-PadP8.37)") (class "Default")
      (node (ref "U$2") (pin "P8.37") (pinfunction "GPIO_78_P8.37") (pintype "bidirectional"))
    )
    (net (code "95") (name "unconnected-(U$2A-GPIO_79-PadP8.38)") (class "Default")
      (node (ref "U$2") (pin "P8.38") (pinfunction "GPIO_79_P8.38") (pintype "bidirectional"))
    )
    (net (code "96") (name "unconnected-(U$2A-GPIO_80-PadP8.36)") (class "Default")
      (node (ref "U$2") (pin "P8.36") (pinfunction "GPIO_80_P8.36") (pintype "bidirectional"))
    )
    (net (code "97") (name "unconnected-(U$2A-GPIO_81-PadP8.34)") (class "Default")
      (node (ref "U$2") (pin "P8.34") (pinfunction "GPIO_81_P8.34") (pintype "bidirectional"))
    )
    (net (code "98") (name "unconnected-(U$2A-GPIO_86-PadP8.27)") (class "Default")
      (node (ref "U$2") (pin "P8.27") (pinfunction "GPIO_86_P8.27") (pintype "bidirectional"))
    )
    (net (code "99") (name "unconnected-(U$2A-GPIO_87-PadP8.29)") (class "Default")
      (node (ref "U$2") (pin "P8.29") (pinfunction "GPIO_87_P8.29") (pintype "bidirectional"))
    )
    (net (code "100") (name "unconnected-(U$2A-GPIO_88-PadP8.28)") (class "Default")
      (node (ref "U$2") (pin "P8.28") (pinfunction "GPIO_88_P8.28") (pintype "bidirectional"))
    )
    (net (code "101") (name "unconnected-(U$2A-GPIO_89-PadP8.30)") (class "Default")
      (node (ref "U$2") (pin "P8.30") (pinfunction "GPIO_89_P8.30") (pintype "bidirectional"))
    )
    (net (code "102") (name "unconnected-(U$2B-AIN0-PadP9.39)") (class "Default")
      (node (ref "U$2") (pin "P9.39") (pinfunction "AIN0_P9.39") (pintype "bidirectional"))
    )
    (net (code "103") (name "unconnected-(U$2B-AIN1-PadP9.40)") (class "Default")
      (node (ref "U$2") (pin "P9.40") (pinfunction "AIN1_P9.40") (pintype "bidirectional"))
    )
    (net (code "104") (name "unconnected-(U$2B-AIN2-PadP9.37)") (class "Default")
      (node (ref "U$2") (pin "P9.37") (pinfunction "AIN2_P9.37") (pintype "bidirectional"))
    )
    (net (code "105") (name "unconnected-(U$2B-AIN3-PadP9.38)") (class "Default")
      (node (ref "U$2") (pin "P9.38") (pinfunction "AIN3_P9.38") (pintype "bidirectional"))
    )
    (net (code "106") (name "unconnected-(U$2B-AIN4-PadP9.33)") (class "Default")
      (node (ref "U$2") (pin "P9.33") (pinfunction "AIN4_P9.33") (pintype "bidirectional"))
    )
    (net (code "107") (name "unconnected-(U$2B-AIN5-PadP9.36)") (class "Default")
      (node (ref "U$2") (pin "P9.36") (pinfunction "AIN5_P9.36") (pintype "bidirectional"))
    )
    (net (code "108") (name "unconnected-(U$2B-AIN6-PadP9.35)") (class "Default")
      (node (ref "U$2") (pin "P9.35") (pinfunction "AIN6_P9.35") (pintype "bidirectional"))
    )
    (net (code "109") (name "unconnected-(U$2B-GNDA_ADC-PadP9.34)") (class "Default")
      (node (ref "U$2") (pin "P9.34") (pinfunction "GNDA_ADC_P9.34") (pintype "bidirectional"))
    )
    (net (code "110") (name "unconnected-(U$2B-GPIO_2-PadP9.22)") (class "Default")
      (node (ref "U$2") (pin "P9.22") (pinfunction "GPIO_2_P9.22") (pintype "bidirectional"))
    )
    (net (code "111") (name "unconnected-(U$2B-GPIO_3-PadP9.21)") (class "Default")
      (node (ref "U$2") (pin "P9.21") (pinfunction "GPIO_3_P9.21") (pintype "bidirectional"))
    )
    (net (code "112") (name "unconnected-(U$2B-GPIO_4-PadP9.17)") (class "Default")
      (node (ref "U$2") (pin "P9.17") (pinfunction "GPIO_4_P9.17") (pintype "bidirectional"))
    )
    (net (code "113") (name "unconnected-(U$2B-GPIO_5-PadP9.18)") (class "Default")
      (node (ref "U$2") (pin "P9.18") (pinfunction "GPIO_5_P9.18") (pintype "bidirectional"))
    )
    (net (code "114") (name "unconnected-(U$2B-GPIO_7-PadP9.42)") (class "Default")
      (node (ref "U$2") (pin "P9.42") (pinfunction "GPIO_7_P9.42") (pintype "bidirectional"))
    )
    (net (code "115") (name "unconnected-(U$2B-GPIO_14-PadP9.26)") (class "Default")
      (node (ref "U$2") (pin "P9.26") (pinfunction "GPIO_14_P9.26") (pintype "bidirectional"))
    )
    (net (code "116") (name "unconnected-(U$2B-GPIO_15-PadP9.24)") (class "Default")
      (node (ref "U$2") (pin "P9.24") (pinfunction "GPIO_15_P9.24") (pintype "bidirectional"))
    )
    (net (code "117") (name "unconnected-(U$2B-GPIO_20-PadP9.41)") (class "Default")
      (node (ref "U$2") (pin "P9.41") (pinfunction "GPIO_20_P9.41") (pintype "bidirectional"))
    )
    (net (code "118") (name "unconnected-(U$2B-GPIO_40-PadP9.14)") (class "Default")
      (node (ref "U$2") (pin "P9.14") (pinfunction "GPIO_40_P9.14") (pintype "bidirectional"))
    )
    (net (code "119") (name "unconnected-(U$2B-GPIO_48-PadP9.15)") (class "Default")
      (node (ref "U$2") (pin "P9.15") (pinfunction "GPIO_48_P9.15") (pintype "bidirectional"))
    )
    (net (code "120") (name "unconnected-(U$2B-GPIO_51-PadP9.16)") (class "Default")
      (node (ref "U$2") (pin "P9.16") (pinfunction "GPIO_51_P9.16") (pintype "bidirectional"))
    )
    (net (code "121") (name "unconnected-(U$2B-GPIO_60-PadP9.12)") (class "Default")
      (node (ref "U$2") (pin "P9.12") (pinfunction "GPIO_60_P9.12") (pintype "bidirectional"))
    )
    (net (code "122") (name "unconnected-(U$2B-GPIO_117-PadP9.25)") (class "Default")
      (node (ref "U$2") (pin "P9.25") (pinfunction "GPIO_117_P9.25") (pintype "bidirectional"))
    )
    (net (code "123") (name "unconnected-(U$2B-GPIO_120-PadP9.31)") (class "Default")
      (node (ref "U$2") (pin "P9.31") (pinfunction "GPIO_120_P9.31") (pintype "bidirectional"))
    )
    (net (code "124") (name "unconnected-(U$2B-GPIO_121-PadP9.29)") (class "Default")
      (node (ref "U$2") (pin "P9.29") (pinfunction "GPIO_121_P9.29") (pintype "bidirectional"))
    )
    (net (code "125") (name "unconnected-(U$2B-GPIO_122-PadP9.30)") (class "Default")
      (node (ref "U$2") (pin "P9.30") (pinfunction "GPIO_122_P9.30") (pintype "bidirectional"))
    )
    (net (code "126") (name "unconnected-(U$2B-GPIO_123-PadP9.28)") (class "Default")
      (node (ref "U$2") (pin "P9.28") (pinfunction "GPIO_123_P9.28") (pintype "bidirectional"))
    )
    (net (code "127") (name "unconnected-(U$2B-GPIO_125-PadP9.27)") (class "Default")
      (node (ref "U$2") (pin "P9.27") (pinfunction "GPIO_125_P9.27") (pintype "bidirectional"))
    )
    (net (code "128") (name "unconnected-(U$2B-PWR_BUT-PadP9.9)") (class "Default")
      (node (ref "U$2") (pin "P9.9") (pinfunction "PWR_BUT_P9.9") (pintype "bidirectional"))
    )
    (net (code "129") (name "unconnected-(U$2B-SYS_5V-PadP9.7)") (class "Default")
      (node (ref "U$2") (pin "P9.7") (pinfunction "SYS_5V_P9.7") (pintype "bidirectional"))
    )
    (net (code "130") (name "unconnected-(U$2B-SYS_5V-PadP9.8)") (class "Default")
      (node (ref "U$2") (pin "P9.8") (pinfunction "SYS_5V_P9.8") (pintype "bidirectional"))
    )
    (net (code "131") (name "unconnected-(U$2B-VDD_5V-PadP9.5)") (class "Default")
      (node (ref "U$2") (pin "P9.5") (pinfunction "VDD_5V_P9.5") (pintype "bidirectional"))
    )
    (net (code "132") (name "unconnected-(U$2B-VDD_5V-PadP9.6)") (class "Default")
      (node (ref "U$2") (pin "P9.6") (pinfunction "VDD_5V_P9.6") (pintype "bidirectional"))
    )
    (net (code "133") (name "unconnected-(U$2B-VDD_ADC-PadP9.32)") (class "Default")
      (node (ref "U$2") (pin "P9.32") (pinfunction "VDD_ADC_P9.32") (pintype "bidirectional"))
    )
    (net (code "134") (name "unconnected-(U1-EN-Pad1)") (class "Default")
      (node (ref "U1") (pin "1") (pinfunction "EN_1") (pintype "bidirectional"))
    )
    (net (code "135") (name "unconnected-(U2-ADC6-Pad19)") (class "Default")
      (node (ref "U2") (pin "19") (pinfunction "ADC6_19") (pintype "bidirectional"))
    )
    (net (code "136") (name "unconnected-(U2-ADC7-Pad22)") (class "Default")
      (node (ref "U2") (pin "22") (pinfunction "ADC7_22") (pintype "bidirectional"))
    )
    (net (code "137") (name "unconnected-(U2-AREF-Pad20)") (class "Default")
      (node (ref "U2") (pin "20") (pinfunction "AREF_20") (pintype "bidirectional"))
    )
  )
)
